# leptonBreakout.net
KiCad netlist of a schematic drawn in EAGLE
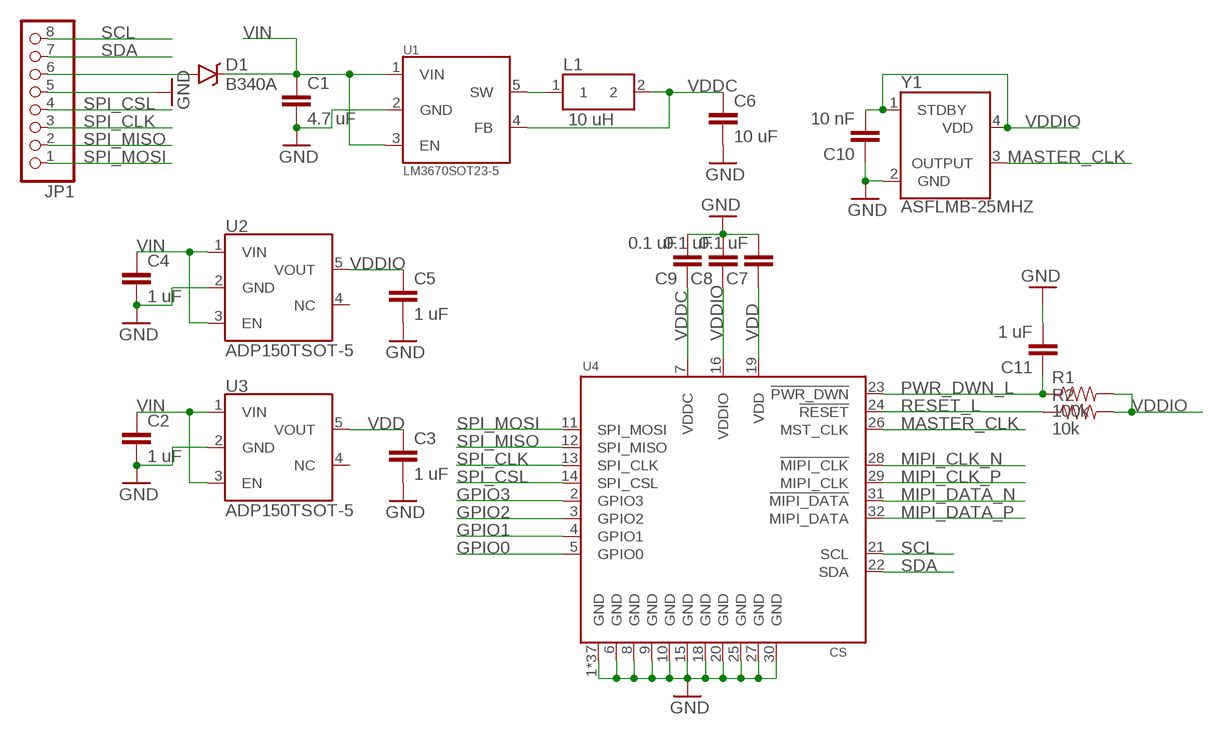
[diagram p0: schematic, sheet 1]

(export (version "E")
  (design (tool "Eeschema 10.0.6"))
  (components
    (comp (ref "C1")
      (value "4.7 uF")
      (footprint "eagle-import:0805")
      (libsource (lib "eagle-import") (part "CAP0805"))
    )
    (comp (ref "C2")
      (value "1 uF")
      (footprint "eagle-import:0805")
      (libsource (lib "eagle-import") (part "CAP0805"))
    )
    (comp (ref "C3")
      (value "1 uF")
      (footprint "eagle-import:0805")
      (libsource (lib "eagle-import") (part "CAP0805"))
    )
    (comp (ref "C4")
      (value "1 uF")
      (footprint "eagle-import:0805")
      (libsource (lib "eagle-import") (part "CAP0805"))
    )
    (comp (ref "C5")
      (value "1 uF")
      (footprint "eagle-import:0805")
      (libsource (lib "eagle-import") (part "CAP0805"))
    )
    (comp (ref "C6")
      (value "10 uF")
      (footprint "eagle-import:0805")
      (libsource (lib "eagle-import") (part "CAP0805"))
    )
    (comp (ref "C7")
      (value "0.1 uF")
      (footprint "eagle-import:0805")
      (libsource (lib "eagle-import") (part "CAP0805"))
    )
    (comp (ref "C8")
      (value "0.1 uF")
      (footprint "eagle-import:0805")
      (libsource (lib "eagle-import") (part "CAP0805"))
    )
    (comp (ref "C9")
      (value "0.1 uF")
      (footprint "eagle-import:0805")
      (libsource (lib "eagle-import") (part "CAP0805"))
    )
    (comp (ref "C10")
      (value "10 nF")
      (footprint "eagle-import:0805")
      (libsource (lib "eagle-import") (part "CAP0805"))
    )
    (comp (ref "C11")
      (value "1 uF")
      (footprint "eagle-import:0805")
      (libsource (lib "eagle-import") (part "CAP0805"))
    )
    (comp (ref "D1")
      (value "B340A")
      (footprint "eagle-import:SMA-DIODE")
      (libsource (lib "eagle-import") (part "DIODE-SCHOTTKY-B340A"))
    )
    (comp (ref "JP1")
      (value "PINHD-1X8/90")
      (footprint "eagle-import:1X08_90")
      (libsource (lib "eagle-import") (part "PINHD-1X8/90"))
    )
    (comp (ref "L1")
      (value "10 uH")
      (footprint "eagle-import:SMD-INDUCTOR")
      (libsource (lib "eagle-import") (part "SMD-INDUCTOR"))
    )
    (comp (ref "R1")
      (value "100k")
      (footprint "eagle-import:0805")
      (libsource (lib "eagle-import") (part "RESISTOR0805-RES"))
    )
    (comp (ref "R2")
      (value "10k")
      (footprint "eagle-import:0805")
      (libsource (lib "eagle-import") (part "RESISTOR0805-RES"))
    )
    (comp (ref "U1")
      (value "LM3670SOT23-5")
      (footprint "eagle-import:SOT23-5")
      (libsource (lib "eagle-import") (part "LM3670SOT23-5"))
    )
    (comp (ref "U2")
      (value "ADP150TSOT-5")
      (footprint "eagle-import:SOT23-5")
      (libsource (lib "eagle-import") (part "ADP150TSOT-5"))
    )
    (comp (ref "U3")
      (value "ADP150TSOT-5")
      (footprint "eagle-import:SOT23-5")
      (libsource (lib "eagle-import") (part "ADP150TSOT-5"))
    )
    (comp (ref "U4")
      (value "CS")
      (footprint "eagle-import:CAM-SOCKET")
      (libsource (lib "eagle-import") (part "CAM-MODULE"))
    )
    (comp (ref "Y1")
      (value "ASFLMB-25MHZ")
      (footprint "eagle-import:5X3.2-CRYSTAL-OSC")
      (libsource (lib "eagle-import") (part "ASFLMB-25MHZ"))
    )
  )
  (nets
    (net (code "1") (name "/GPIO0") (class "Default")
      (node (ref "U4") (pin "5") (pinfunction "GPIO0_5") (pintype "bidirectional"))
    )
    (net (code "2") (name "/GPIO1") (class "Default")
      (node (ref "U4") (pin "4") (pinfunction "GPIO1_4") (pintype "bidirectional"))
    )
    (net (code "3") (name "/GPIO2") (class "Default")
      (node (ref "U4") (pin "3") (pinfunction "GPIO2_3") (pintype "bidirectional"))
    )
    (net (code "4") (name "/GPIO3") (class "Default")
      (node (ref "U4") (pin "2") (pinfunction "GPIO3_2") (pintype "bidirectional"))
    )
    (net (code "5") (name "/MASTER_CLK") (class "Default")
      (node (ref "U4") (pin "26") (pinfunction "MST_CLK_26") (pintype "bidirectional"))
      (node (ref "Y1") (pin "3") (pinfunction "OUTPUT_3") (pintype "bidirectional"))
    )
    (net (code "6") (name "/MIPI_CLK_N") (class "Default")
      (node (ref "U4") (pin "28") (pinfunction "~{MIPI_CLK}_28") (pintype "bidirectional"))
    )
    (net (code "7") (name "/MIPI_CLK_P") (class "Default")
      (node (ref "U4") (pin "29") (pinfunction "MIPI_CLK_29") (pintype "bidirectional"))
    )
    (net (code "8") (name "/MIPI_DATA_N") (class "Default")
      (node (ref "U4") (pin "31") (pinfunction "~{MIPI_DATA}_31") (pintype "bidirectional"))
    )
    (net (code "9") (name "/MIPI_DATA_P") (class "Default")
      (node (ref "U4") (pin "32") (pinfunction "MIPI_DATA_32") (pintype "bidirectional"))
    )
    (net (code "10") (name "/PWR_DWN_L") (class "Default")
      (node (ref "C11") (pin "1") (pinfunction "1_1") (pintype "passive"))
      (node (ref "R1") (pin "1") (pinfunction "1_1") (pintype "passive"))
      (node (ref "U4") (pin "23") (pinfunction "~{PWR_DWN}_23") (pintype "bidirectional"))
    )
    (net (code "11") (name "/RESET_L") (class "Default")
      (node (ref "R2") (pin "1") (pinfunction "1_1") (pintype "passive"))
      (node (ref "U4") (pin "24") (pinfunction "~{RESET}_24") (pintype "bidirectional"))
    )
    (net (code "12") (name "/SCL") (class "Default")
      (node (ref "JP1") (pin "8") (pinfunction "8_8") (pintype "passive"))
      (node (ref "U4") (pin "21") (pinfunction "SCL_21") (pintype "bidirectional"))
    )
    (net (code "13") (name "/SDA") (class "Default")
      (node (ref "JP1") (pin "7") (pinfunction "7_7") (pintype "passive"))
      (node (ref "U4") (pin "22") (pinfunction "SDA_22") (pintype "bidirectional"))
    )
    (net (code "14") (name "/SPI_CLK") (class "Default")
      (node (ref "JP1") (pin "3") (pinfunction "3_3") (pintype "passive"))
      (node (ref "U4") (pin "13") (pinfunction "SPI_CLK_13") (pintype "bidirectional"))
    )
    (net (code "15") (name "/SPI_CSL") (class "Default")
      (node (ref "JP1") (pin "4") (pinfunction "4_4") (pintype "passive"))
      (node (ref "U4") (pin "14") (pinfunction "SPI_CSL_14") (pintype "bidirectional"))
    )
    (net (code "16") (name "/SPI_MISO") (class "Default")
      (node (ref "JP1") (pin "2") (pinfunction "2_2") (pintype "passive"))
      (node (ref "U4") (pin "12") (pinfunction "SPI_MISO_12") (pintype "bidirectional"))
    )
    (net (code "17") (name "/SPI_MOSI") (class "Default")
      (node (ref "JP1") (pin "1") (pinfunction "1_1") (pintype "passive"))
      (node (ref "U4") (pin "11") (pinfunction "SPI_MOSI_11") (pintype "bidirectional"))
    )
    (net (code "18") (name "/VDD") (class "Default")
      (node (ref "C3") (pin "1") (pinfunction "1_1") (pintype "passive"))
      (node (ref "C7") (pin "1") (pinfunction "1_1") (pintype "passive"))
      (node (ref "U3") (pin "5") (pinfunction "VOUT_5") (pintype "power_in"))
      (node (ref "U4") (pin "19") (pinfunction "VDD_19") (pintype "power_in"))
    )
    (net (code "19") (name "/VDDC") (class "Default")
      (node (ref "C6") (pin "1") (pinfunction "1_1") (pintype "passive"))
      (node (ref "C9") (pin "1") (pinfunction "1_1") (pintype "passive"))
      (node (ref "L1") (pin "2") (pinfunction "2_2") (pintype "bidirectional"))
      (node (ref "U1") (pin "4") (pinfunction "FB_4") (pintype "bidirectional"))
      (node (ref "U4") (pin "7") (pinfunction "VDDC_7") (pintype "power_in"))
    )
    (net (code "20") (name "/VDDIO") (class "Default")
      (node (ref "C10") (pin "2") (pinfunction "2_2") (pintype "passive"))
      (node (ref "C5") (pin "1") (pinfunction "1_1") (pintype "passive"))
      (node (ref "C8") (pin "1") (pinfunction "1_1") (pintype "passive"))
      (node (ref "R1") (pin "2") (pinfunction "2_2") (pintype "passive"))
      (node (ref "R2") (pin "2") (pinfunction "2_2") (pintype "passive"))
      (node (ref "U2") (pin "5") (pinfunction "VOUT_5") (pintype "power_in"))
      (node (ref "U4") (pin "16") (pinfunction "VDDIO_16") (pintype "power_in"))
      (node (ref "Y1") (pin "1") (pinfunction "STDBY_1") (pintype "bidirectional"))
      (node (ref "Y1") (pin "4") (pinfunction "VDD_4") (pintype "power_in"))
    )
    (net (code "21") (name "/VIN") (class "Default")
      (node (ref "C1") (pin "1") (pinfunction "1_1") (pintype "passive"))
      (node (ref "C2") (pin "1") (pinfunction "1_1") (pintype "passive"))
      (node (ref "C4") (pin "1") (pinfunction "1_1") (pintype "passive"))
      (node (ref "D1") (pin "C") (pinfunction "C_C") (pintype "passive"))
      (node (ref "U1") (pin "1") (pinfunction "VIN_1") (pintype "power_in"))
      (node (ref "U1") (pin "3") (pinfunction "EN_3") (pintype "bidirectional"))
      (node (ref "U2") (pin "1") (pinfunction "VIN_1") (pintype "power_in"))
      (node (ref "U2") (pin "3") (pinfunction "EN_3") (pintype "bidirectional"))
      (node (ref "U3") (pin "1") (pinfunction "VIN_1") (pintype "power_in"))
      (node (ref "U3") (pin "3") (pinfunction "EN_3") (pintype "bidirectional"))
    )
    (net (code "22") (name "GND") (class "Default")
      (node (ref "C1") (pin "2") (pinfunction "2_2") (pintype "passive"))
      (node (ref "C10") (pin "1") (pinfunction "1_1") (pintype "passive"))
      (node (ref "C11") (pin "2") (pinfunction "2_2") (pintype "passive"))
      (node (ref "C2") (pin "2") (pinfunction "2_2") (pintype "passive"))
      (node (ref "C3") (pin "2") (pinfunction "2_2") (pintype "passive"))
      (node (ref "C4") (pin "2") (pinfunction "2_2") (pintype "passive"))
      (node (ref "C5") (pin "2") (pinfunction "2_2") (pintype "passive"))
      (node (ref "C6") (pin "2") (pinfunction "2_2") (pintype "passive"))
      (node (ref "C7") (pin "2") (pinfunction "2_2") (pintype "passive"))
      (node (ref "C8") (pin "2") (pinfunction "2_2") (pintype "passive"))
      (node (ref "C9") (pin "2") (pinfunction "2_2") (pintype "passive"))
      (node (ref "JP1") (pin "5") (pinfunction "5_5") (pintype "passive"))
      (node (ref "U1") (pin "2") (pinfunction "GND_2") (pintype "power_in"))
      (node (ref "U2") (pin "2") (pinfunction "GND_2") (pintype "power_in"))
      (node (ref "U3") (pin "2") (pinfunction "GND_2") (pintype "power_in"))
      (node (ref "U4") (pin "1") (pinfunction "GND_1") (pintype "power_in"))
      (node (ref "U4") (pin "10") (pinfunction "GND_10") (pintype "power_in"))
      (node (ref "U4") (pin "15") (pinfunction "GND_15") (pintype "power_in"))
      (node (ref "U4") (pin "18") (pinfunction "GND_18") (pintype "power_in"))
      (node (ref "U4") (pin "20") (pinfunction "GND_20") (pintype "power_in"))
      (node (ref "U4") (pin "25") (pinfunction "GND_25") (pintype "power_in"))
      (node (ref "U4") (pin "27") (pinfunction "GND_27") (pintype "power_in"))
      (node (ref "U4") (pin "30") (pinfunction "GND_30") (pintype "power_in"))
      (node (ref "U4") (pin "6") (pinfunction "GND_6") (pintype "power_in"))
      (node (ref "U4") (pin "8") (pinfunction "GND_8") (pintype "power_in"))
      (node (ref "U4") (pin "9") (pinfunction "GND_9") (pintype "power_in"))
      (node (ref "U4") (pin "P$1") (pinfunction "GND_P$1") (pintype "power_in"))
      (node (ref "U4") (pin "P$10") (pinfunction "GND_P$10") (pintype "power_in"))
      (node (ref "U4") (pin "P$11") (pinfunction "GND_P$11") (pintype "power_in"))
      (node (ref "U4") (pin "P$12") (pinfunction "GND_P$12") (pintype "power_in"))
      (node (ref "U4") (pin "P$13") (pinfunction "GND_P$13") (pintype "power_in"))
      (node (ref "U4") (pin "P$14") (pinfunction "GND_P$14") (pintype "power_in"))
      (node (ref "U4") (pin "P$15") (pinfunction "GND_P$15") (pintype "power_in"))
      (node (ref "U4") (pin "P$16") (pinfunction "GND_P$16") (pintype "power_in"))
      (node (ref "U4") (pin "P$17") (pinfunction "GND_P$17") (pintype "power_in"))
      (node (ref "U4") (pin "P$18") (pinfunction "GND_P$18") (pintype "power_in"))
      (node (ref "U4") (pin "P$19") (pinfunction "GND_P$19") (pintype "power_in"))
      (node (ref "U4") (pin "P$2") (pinfunction "GND_P$2") (pintype "power_in"))
      (node (ref "U4") (pin "P$20") (pinfunction "GND_P$20") (pintype "power_in"))
      (node (ref "U4") (pin "P$21") (pinfunction "GND_P$21") (pintype "power_in"))
      (node (ref "U4") (pin "P$22") (pinfunction "GND_P$22") (pintype "power_in"))
      (node (ref "U4") (pin "P$23") (pinfunction "GND_P$23") (pintype "power_in"))
      (node (ref "U4") (pin "P$24") (pinfunction "GND_P$24") (pintype "power_in"))
      (node (ref "U4") (pin "P$25") (pinfunction "GND_P$25") (pintype "power_in"))
      (node (ref "U4") (pin "P$26") (pinfunction "GND_P$26") (pintype "power_in"))
      (node (ref "U4") (pin "P$27") (pinfunction "GND_P$27") (pintype "power_in"))
      (node (ref "U4") (pin "P$28") (pinfunction "GND_P$28") (pintype "power_in"))
      (node (ref "U4") (pin "P$29") (pinfunction "GND_P$29") (pintype "power_in"))
      (node (ref "U4") (pin "P$3") (pinfunction "GND_P$3") (pintype "power_in"))
      (node (ref "U4") (pin "P$30") (pinfunction "GND_P$30") (pintype "power_in"))
      (node (ref "U4") (pin "P$31") (pinfunction "GND_P$31") (pintype "power_in"))
      (node (ref "U4") (pin "P$32") (pinfunction "GND_P$32") (pintype "power_in"))
      (node (ref "U4") (pin "P$33") (pinfunction "GND_P$33") (pintype "power_in"))
      (node (ref "U4") (pin "P$34") (pinfunction "GND_P$34") (pintype "power_in"))
      (node (ref "U4") (pin "P$35") (pinfunction "GND_P$35") (pintype "power_in"))
      (node (ref "U4") (pin "P$36") (pinfunction "GND_P$36") (pintype "power_in"))
      (node (ref "U4") (pin "P$4") (pinfunction "GND_P$4") (pintype "power_in"))
      (node (ref "U4") (pin "P$5") (pinfunction "GND_P$5") (pintype "power_in"))
      (node (ref "U4") (pin "P$6") (pinfunction "GND_P$6") (pintype "power_in"))
      (node (ref "U4") (pin "P$7") (pinfunction "GND_P$7") (pintype "power_in"))
      (node (ref "U4") (pin "P$8") (pinfunction "GND_P$8") (pintype "power_in"))
      (node (ref "U4") (pin "P$9") (pinfunction "GND_P$9") (pintype "power_in"))
      (node (ref "Y1") (pin "2") (pinfunction "GND_2") (pintype "power_in"))
    )
    (net (code "23") (name "Net-(D1-PadA)") (class "Default")
      (node (ref "D1") (pin "A") (pinfunction "A_A") (pintype "passive"))
      (node (ref "JP1") (pin "6") (pinfunction "6_6") (pintype "passive"))
    )
    (net (code "24") (name "Net-(U1-SW)") (class "Default")
      (node (ref "L1") (pin "1") (pinfunction "1_1") (pintype "bidirectional"))
      (node (ref "U1") (pin "5") (pinfunction "SW_5") (pintype "power_in"))
    )
    (net (code "25") (name "unconnected-(U2-NC-Pad4)") (class "Default")
      (node (ref "U2") (pin "4") (pinfunction "NC_4") (pintype "bidirectional"))
    )
    (net (code "26") (name "unconnected-(U3-NC-Pad4)") (class "Default")
      (node (ref "U3") (pin "4") (pinfunction "NC_4") (pintype "bidirectional"))
    )
  )
)
